# Cameras_v3.net
KiCad netlist of a schematic drawn in Altium Designer
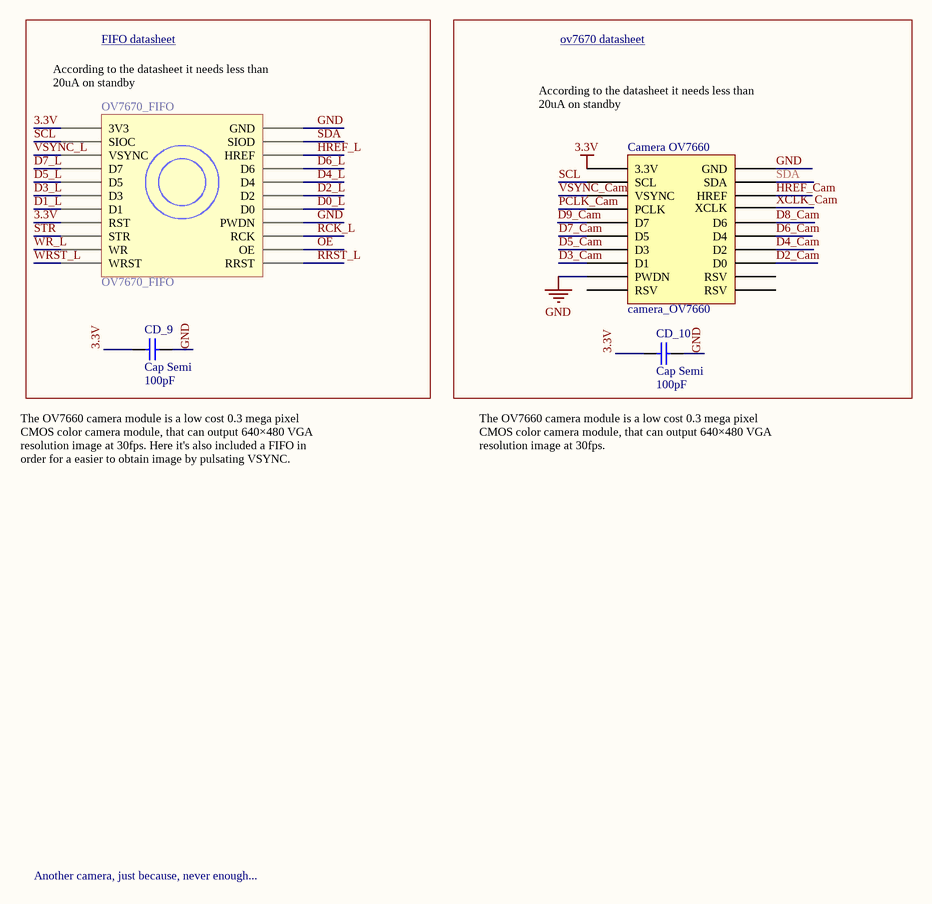
[diagram p0: Cameras_v3.SchDoc]

(export (version "E")
  (design (tool "Eeschema 10.0.6"))
  (components
    (comp (ref "Camera OV7660")
      (value "camera_OV7660")
      (footprint "CAMERA_OV7660 - high - Pins")
      (libsource (lib "Trackuino_Shield") (part "camera_OV7660"))
    )
    (comp (ref "CD_9")
      (value "Cap Semi")
      (footprint "C1206")
      (description "Capacitor (Semiconductor SIM Model)")
      (fields (field (name "ALTIUM_VALUE") "100pF") (field (name "PUBLISHER") "Altium Limited"))
      (libsource (lib "Miscellaneous Devices") (part "Cap Semi"))
    )
    (comp (ref "CD_10")
      (value "Cap Semi")
      (footprint "C1206")
      (description "Capacitor (Semiconductor SIM Model)")
      (fields (field (name "ALTIUM_VALUE") "100pF") (field (name "PUBLISHER") "Altium Limited"))
      (libsource (lib "Miscellaneous Devices") (part "Cap Semi"))
    )
    (comp (ref "OV7670_FIFO")
      (value "OV7670_FIFO")
      (footprint "OV7670_FIFO_SIDE_PINS")
      (libsource (lib "Trackuino_Shield") (part "OV7670_FIFO_FRONT_PINS"))
    )
  )
  (nets
    (net (code "1") (name "/D0_L") (class "Default")
      (node (ref "OV7670_FIFO") (pin "D0") (pinfunction "D0_D0") (pintype "passive"))
    )
    (net (code "2") (name "/D1_L") (class "Default")
      (node (ref "OV7670_FIFO") (pin "D1") (pinfunction "D1_D1") (pintype "passive"))
    )
    (net (code "3") (name "/D2_Cam") (class "Default")
      (node (ref "Camera OV7660") (pin "D0") (pinfunction "D0_D0") (pintype "passive"))
    )
    (net (code "4") (name "/D2_L") (class "Default")
      (node (ref "OV7670_FIFO") (pin "D2") (pinfunction "D2_D2") (pintype "passive"))
    )
    (net (code "5") (name "/D3_Cam") (class "Default")
      (node (ref "Camera OV7660") (pin "D1") (pinfunction "D1_D1") (pintype "passive"))
    )
    (net (code "6") (name "/D3_L") (class "Default")
      (node (ref "OV7670_FIFO") (pin "D3") (pinfunction "D3_D3") (pintype "passive"))
    )
    (net (code "7") (name "/D4_Cam") (class "Default")
      (node (ref "Camera OV7660") (pin "D2") (pinfunction "D2_D2") (pintype "passive"))
    )
    (net (code "8") (name "/D4_L") (class "Default")
      (node (ref "OV7670_FIFO") (pin "D4") (pinfunction "D4_D4") (pintype "passive"))
    )
    (net (code "9") (name "/D5_Cam") (class "Default")
      (node (ref "Camera OV7660") (pin "D3") (pinfunction "D3_D3") (pintype "passive"))
    )
    (net (code "10") (name "/D5_L") (class "Default")
      (node (ref "OV7670_FIFO") (pin "D5") (pinfunction "D5_D5") (pintype "passive"))
    )
    (net (code "11") (name "/D6_Cam") (class "Default")
      (node (ref "Camera OV7660") (pin "D4") (pinfunction "D4_D4") (pintype "passive"))
    )
    (net (code "12") (name "/D6_L") (class "Default")
      (node (ref "OV7670_FIFO") (pin "D6") (pinfunction "D6_D6") (pintype "passive"))
    )
    (net (code "13") (name "/D7_Cam") (class "Default")
      (node (ref "Camera OV7660") (pin "D5") (pinfunction "D5_D5") (pintype "passive"))
    )
    (net (code "14") (name "/D7_L") (class "Default")
      (node (ref "OV7670_FIFO") (pin "D7") (pinfunction "D7_D7") (pintype "passive"))
    )
    (net (code "15") (name "/D8_Cam") (class "Default")
      (node (ref "Camera OV7660") (pin "D6") (pinfunction "D6_D6") (pintype "passive"))
    )
    (net (code "16") (name "/D9_Cam") (class "Default")
      (node (ref "Camera OV7660") (pin "D7") (pinfunction "D7_D7") (pintype "passive"))
    )
    (net (code "17") (name "/HREF_Cam") (class "Default")
      (node (ref "Camera OV7660") (pin "HREF") (pinfunction "HREF_HREF") (pintype "passive"))
    )
    (net (code "18") (name "/HREF_L") (class "Default")
      (node (ref "OV7670_FIFO") (pin "HREF") (pinfunction "HREF_HREF") (pintype "passive"))
    )
    (net (code "19") (name "/OE") (class "Default")
      (node (ref "OV7670_FIFO") (pin "OE") (pinfunction "OE_OE") (pintype "passive"))
    )
    (net (code "20") (name "/PCLK_Cam") (class "Default")
      (node (ref "Camera OV7660") (pin "PCLK") (pinfunction "PCLK_PCLK") (pintype "passive"))
    )
    (net (code "21") (name "/RCK_L") (class "Default")
      (node (ref "OV7670_FIFO") (pin "RCK") (pinfunction "RCK_RCK") (pintype "passive"))
    )
    (net (code "22") (name "/RRST_L") (class "Default")
      (node (ref "OV7670_FIFO") (pin "RRST") (pinfunction "RRST_RRST") (pintype "passive"))
    )
    (net (code "23") (name "/SCL") (class "Default")
      (node (ref "Camera OV7660") (pin "SCL") (pinfunction "SCL_SCL") (pintype "open_collector"))
      (node (ref "OV7670_FIFO") (pin "SIOC") (pinfunction "SIOC_SIOC") (pintype "passive"))
    )
    (net (code "24") (name "/SDA") (class "Default")
      (node (ref "Camera OV7660") (pin "SDA") (pinfunction "SDA_SDA") (pintype "passive"))
      (node (ref "OV7670_FIFO") (pin "SIOD") (pinfunction "SIOD_SIOD") (pintype "passive"))
    )
    (net (code "25") (name "/STR") (class "Default")
      (node (ref "OV7670_FIFO") (pin "STR") (pinfunction "STR_STR") (pintype "passive"))
    )
    (net (code "26") (name "/VSYNC_Cam") (class "Default")
      (node (ref "Camera OV7660") (pin "VSYNC") (pinfunction "VSYNC_VSYNC") (pintype "passive"))
    )
    (net (code "27") (name "/VSYNC_L") (class "Default")
      (node (ref "OV7670_FIFO") (pin "VSYNC") (pinfunction "VSYNC_VSYNC") (pintype "passive"))
    )
    (net (code "28") (name "/WRST_L") (class "Default")
      (node (ref "OV7670_FIFO") (pin "WRST") (pinfunction "WRST_WRST") (pintype "passive"))
    )
    (net (code "29") (name "/WR_L") (class "Default")
      (node (ref "OV7670_FIFO") (pin "WR") (pinfunction "WR_WR") (pintype "passive"))
    )
    (net (code "30") (name "/XCLK_Cam") (class "Default")
      (node (ref "Camera OV7660") (pin "XCLK") (pinfunction "XCLK_XCLK") (pintype "passive"))
    )
    (net (code "31") (name "3.3V") (class "Default")
      (node (ref "CD_10") (pin "2") (pinfunction "2_2") (pintype "passive"))
      (node (ref "CD_9") (pin "2") (pinfunction "2_2") (pintype "passive"))
      (node (ref "Camera OV7660") (pin "3V3") (pinfunction "3.3V_3V3") (pintype "passive"))
      (node (ref "OV7670_FIFO") (pin "3V3") (pinfunction "3V3_3V3") (pintype "passive"))
      (node (ref "OV7670_FIFO") (pin "RST") (pinfunction "RST_RST") (pintype "passive"))
    )
    (net (code "32") (name "GND") (class "Default")
      (node (ref "CD_10") (pin "1") (pinfunction "1_1") (pintype "passive"))
      (node (ref "CD_9") (pin "1") (pinfunction "1_1") (pintype "passive"))
      (node (ref "Camera OV7660") (pin "GND") (pinfunction "GND_GND") (pintype "passive"))
      (node (ref "Camera OV7660") (pin "PWDN") (pinfunction "PWDN_PWDN") (pintype "passive"))
      (node (ref "OV7670_FIFO") (pin "GND") (pinfunction "GND_GND") (pintype "passive"))
      (node (ref "OV7670_FIFO") (pin "PWDN") (pinfunction "PWDN_PWDN") (pintype "passive"))
    )
    (net (code "33") (name "unconnected-(Camera OV7660-RSV-PadRSV1)") (class "Default")
      (node (ref "Camera OV7660") (pin "RSV1") (pinfunction "RSV_RSV1") (pintype "passive"))
    )
    (net (code "34") (name "unconnected-(Camera OV7660-RSV-PadRSV2)") (class "Default")
      (node (ref "Camera OV7660") (pin "RSV2") (pinfunction "RSV_RSV2") (pintype "passive"))
    )
    (net (code "35") (name "unconnected-(Camera OV7660-RSV-PadRSV3)") (class "Default")
      (node (ref "Camera OV7660") (pin "RSV3") (pinfunction "RSV_RSV3") (pintype "passive"))
    )
  )
)
